# vreg.net
KiCad netlist of a schematic drawn in Altium Designer
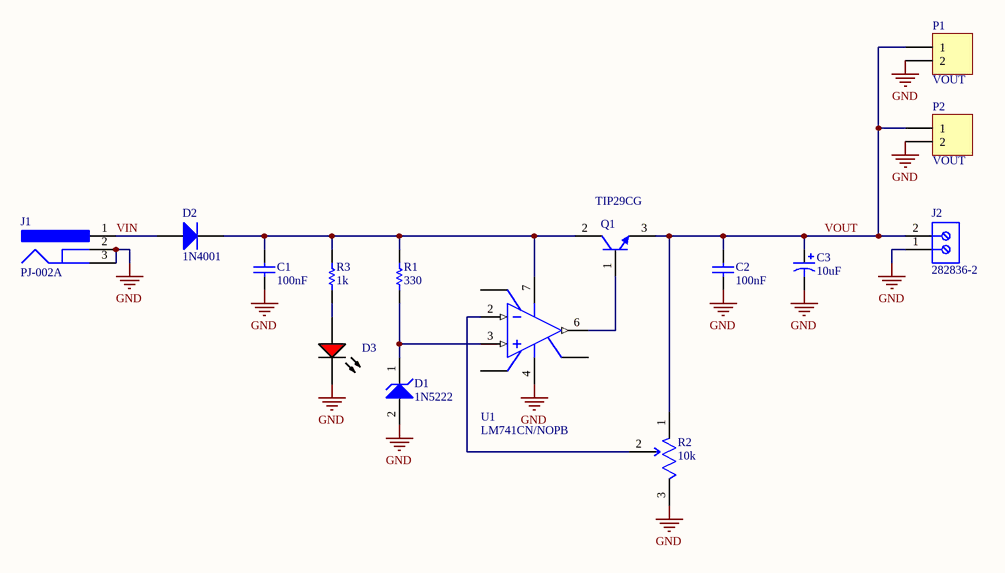
[diagram p0: vreg.SchDoc]

(export (version "E")
  (design (tool "Eeschema 10.0.6"))
  (components
    (comp (ref "C1")
      (value "100nF")
      (footprint "Miscellaneous Devices:RAD-0.1")
      (description "Capacitor")
      (fields
        (field (name "PARTNUMBER") "399-4151-ND")
        (field (name "Comment") "Cap")
        (field (name "PUBLISHER") "Altium Limited")
      )
      (libsource (lib "Miscellaneous Devices") (part "Cap"))
    )
    (comp (ref "C2")
      (value "100nF")
      (footprint "Miscellaneous Devices:RAD-0.1")
      (description "Capacitor")
      (fields
        (field (name "PARTNUMBER") "399-4151-ND")
        (field (name "Comment") "Cap")
        (field (name "PUBLISHER") "Altium Limited")
      )
      (libsource (lib "Miscellaneous Devices") (part "Cap"))
    )
    (comp (ref "C3")
      (value "10uF")
      (footprint "RAD-0.1")
      (description "Polarized Capacitor (Radial)")
      (fields (field (name "Comment") "Cap Pol1") (field (name "PUBLISHER") "Altium Limited"))
      (libsource (lib "Miscellaneous Devices") (part "Cap Pol1"))
    )
    (comp (ref "D1")
      (value "1N5222")
      (footprint "ONSC-SURMETIC40-2-017AA-01")
      (description "5 W Zener Voltage Regulator, 2-Pin Surmetic(TM) 40, Pb-Free, Tape and Reel")
      (fields (field (name "MANUFACTURER") "On Semiconductor") (field (name "PARTNUMBER") "1N5222B-ND"))
      (libsource (lib "Altium Content Vault") (part "ONSC-K1A2-2"))
    )
    (comp (ref "D2")
      (value "1N4001")
      (footprint "DO-41")
      (description "1 Amp General Purpose Rectifier")
      (fields (field (name "PARTNUMBER") "S1011EC-04-ND") (field (name "PUBLISHER") "Altium Limited"))
      (libsource (lib "Miscellaneous Devices") (part "Diode 1N4001"))
    )
    (comp (ref "D3")
      (value "HLMP-3301")
      (footprint "AVAG-HLMP-3301-2")
      (description "T-1 3/4 (5 mm) Diffused LED Lamp, 1.9 V, -40 to 100 degC, 2-Pin THD, RoHS, Bulk")
      (fields (field (name "MANUFACTURER") "Avago") (field (name "PARTNUMBER") "1497-XCMDK12D-ND"))
      (libsource (lib "Altium Content Vault") (part "LED-RED-K1A2-2"))
    )
    (comp (ref "J1")
      (value "PJ-002A")
      (footprint "CUI-PJ-002A_V")
      (fields (field (name "MANUFACTURER") "CUIInc.") (field (name "PARTNUMBER") "CP-002A-ND"))
      (libsource (lib "Altium Content Vault") (part "JACK-2CD3-RN"))
    )
    (comp (ref "J2")
      (value "282836-2")
      (footprint "TECO-282836-2_V")
      (description "Female Header, Pitch 5 mm, 1 x 2 Position, Height 10 mm, Tail Length 3.5 mm, Rohs, Bulk")
      (fields (field (name "VOLTAGE") "300V") (field (name "MANUFACTURER") "TE Connectivity"))
      (libsource (lib "Altium Content Vault") (part "CN-1P-F-TB2"))
    )
    (comp (ref "P1")
      (value "VOUT")
      (footprint "HDR1X2")
      (description "Header, 2-Pin")
      (fields (field (name "PARTNUMBER") "S1011EC-04-ND") (field (name "PUBLISHER") "Altium Limited"))
      (libsource (lib "Miscellaneous Connectors") (part "Header 2"))
    )
    (comp (ref "P2")
      (value "VOUT")
      (footprint "HDR1X2")
      (description "Header, 2-Pin")
      (fields (field (name "PARTNUMBER") "S1011EC-04-ND") (field (name "PUBLISHER") "Altium Limited"))
      (libsource (lib "Miscellaneous Connectors") (part "Header 2"))
    )
    (comp (ref "Q1")
      (value "TIP29CG")
      (footprint "ONSC-TO-220-3-221A-09")
      (description "Complementary Silicon Plastic Power Transistor, 3-Pin TO-220, Pb-Free, Tube")
      (fields (field (name "MANUFACTURER") "On Semiconductor") (field (name "PARTNUMBER") "TIP29CGOS-ND"))
      (libsource (lib "Altium Content Vault") (part "ONSC-NPN-B1C2E3-3_C"))
    )
    (comp (ref "R1")
      (value "330")
      (footprint "RAD-0.1")
      (description "Resistor")
      (fields
        (field (name "PARTNUMBER") "330QBK-ND")
        (field (name "Comment") "Res1")
        (field (name "PUBLISHER") "Altium Limited")
      )
      (libsource (lib "Miscellaneous Devices") (part "Res1"))
    )
    (comp (ref "R2")
      (value "10k")
      (footprint "FP-PV37W103C01B00-MFG")
      (description "TRIMMER 10K OHM 0.25W PC PIN TOP PV37W103C01B00")
      (fields (field (name "TOLERANCE") "10%") (field (name "PARTNUMBER") "490-2970-ND"))
      (libsource (lib "Altium Content Vault") (part "d579d08a39777ccaa720d62023d89b1"))
    )
    (comp (ref "R3")
      (value "1k")
      (footprint "AXIAL-0.4")
      (description "Resistor")
      (fields
        (field (name "PARTNUMBER") "CF14JT1K00CT-ND")
        (field (name "Comment") "Res1")
        (field (name "PUBLISHER") "Altium Limited")
      )
      (libsource (lib "Miscellaneous Devices") (part "Res1"))
    )
    (comp (ref "U1")
      (value "LM741CN/NOPB")
      (footprint "P0008A")
      (description "Operational Amplifier, 8-pin MDIP, Pb-Free")
      (fields
        (field (name "PARTNUMBER") "LM741CNNS/NOPB-ND")
        (field (name "MANUFACTURER") "Texas Instruments")
      )
      (libsource (lib "Altium Content Vault") (part "AMP-OPA-LM741-8"))
    )
  )
  (nets
    (net (code "1") (name "/VIN") (class "Default")
      (node (ref "D2") (pin "1") (pinfunction "A_1") (pintype "passive"))
      (node (ref "J1") (pin "1") (pinfunction "1_1") (pintype "passive"))
    )
    (net (code "2") (name "/VOUT") (class "Default")
      (node (ref "C2") (pin "1") (pinfunction "1_1") (pintype "passive"))
      (node (ref "C3") (pin "1") (pinfunction "1_1") (pintype "passive"))
      (node (ref "J2") (pin "2") (pinfunction "2_2") (pintype "passive"))
      (node (ref "P1") (pin "1") (pinfunction "1_1") (pintype "passive"))
      (node (ref "P2") (pin "1") (pinfunction "1_1") (pintype "passive"))
      (node (ref "Q1") (pin "3") (pinfunction "E_3") (pintype "passive"))
      (node (ref "R2") (pin "1") (pinfunction "1_1") (pintype "passive"))
    )
    (net (code "3") (name "GND") (class "Default")
      (node (ref "C1") (pin "2") (pinfunction "2_2") (pintype "passive"))
      (node (ref "C2") (pin "2") (pinfunction "2_2") (pintype "passive"))
      (node (ref "C3") (pin "2") (pinfunction "2_2") (pintype "passive"))
      (node (ref "D1") (pin "2") (pinfunction "A_2") (pintype "passive"))
      (node (ref "D3") (pin "1") (pinfunction "K_1") (pintype "passive"))
      (node (ref "J1") (pin "2") (pinfunction "2_2") (pintype "passive"))
      (node (ref "J1") (pin "3") (pinfunction "3_3") (pintype "passive"))
      (node (ref "J2") (pin "1") (pinfunction "1_1") (pintype "passive"))
      (node (ref "P1") (pin "2") (pinfunction "2_2") (pintype "passive"))
      (node (ref "P2") (pin "2") (pinfunction "2_2") (pintype "passive"))
      (node (ref "R2") (pin "3") (pinfunction "3_3") (pintype "passive"))
      (node (ref "U1") (pin "4") (pinfunction "V-_4") (pintype "power_in"))
    )
    (net (code "4") (name "Net-(D1-K)") (class "Default")
      (node (ref "D1") (pin "1") (pinfunction "K_1") (pintype "passive"))
      (node (ref "R1") (pin "1") (pinfunction "1_1") (pintype "passive"))
      (node (ref "U1") (pin "3") (pinfunction "IN+_3") (pintype "input"))
    )
    (net (code "5") (name "Net-(D2-K)") (class "Default")
      (node (ref "C1") (pin "1") (pinfunction "1_1") (pintype "passive"))
      (node (ref "D2") (pin "2") (pinfunction "K_2") (pintype "passive"))
      (node (ref "Q1") (pin "2") (pinfunction "C_2") (pintype "passive"))
      (node (ref "R1") (pin "2") (pinfunction "2_2") (pintype "passive"))
      (node (ref "R3") (pin "2") (pinfunction "2_2") (pintype "passive"))
      (node (ref "U1") (pin "7") (pinfunction "V+_7") (pintype "power_in"))
    )
    (net (code "6") (name "Net-(D3-A)") (class "Default")
      (node (ref "D3") (pin "2") (pinfunction "A_2") (pintype "passive"))
      (node (ref "R3") (pin "1") (pinfunction "1_1") (pintype "passive"))
    )
    (net (code "7") (name "Net-(Q1-B)") (class "Default")
      (node (ref "Q1") (pin "1") (pinfunction "B_1") (pintype "passive"))
      (node (ref "U1") (pin "6") (pinfunction "OUT_6") (pintype "output"))
    )
    (net (code "8") (name "Net-(U1-IN-)") (class "Default")
      (node (ref "R2") (pin "2") (pinfunction "2_2") (pintype "passive"))
      (node (ref "U1") (pin "2") (pinfunction "IN-_2") (pintype "input"))
    )
    (net (code "9") (name "unconnected-(U1-NC-Pad8)") (class "Default")
      (node (ref "U1") (pin "8") (pinfunction "NC_8") (pintype "passive"))
    )
    (net (code "10") (name "unconnected-(U1-OFS_NULL-Pad1)") (class "Default")
      (node (ref "U1") (pin "1") (pinfunction "OFS_NULL_1") (pintype "passive"))
    )
    (net (code "11") (name "unconnected-(U1-OFS_NULL-Pad5)") (class "Default")
      (node (ref "U1") (pin "5") (pinfunction "OFS_NULL_5") (pintype "passive"))
    )
  )
)
